# Power_driver_DAC_Connectors.net
KiCad netlist of a schematic drawn in Altium Designer
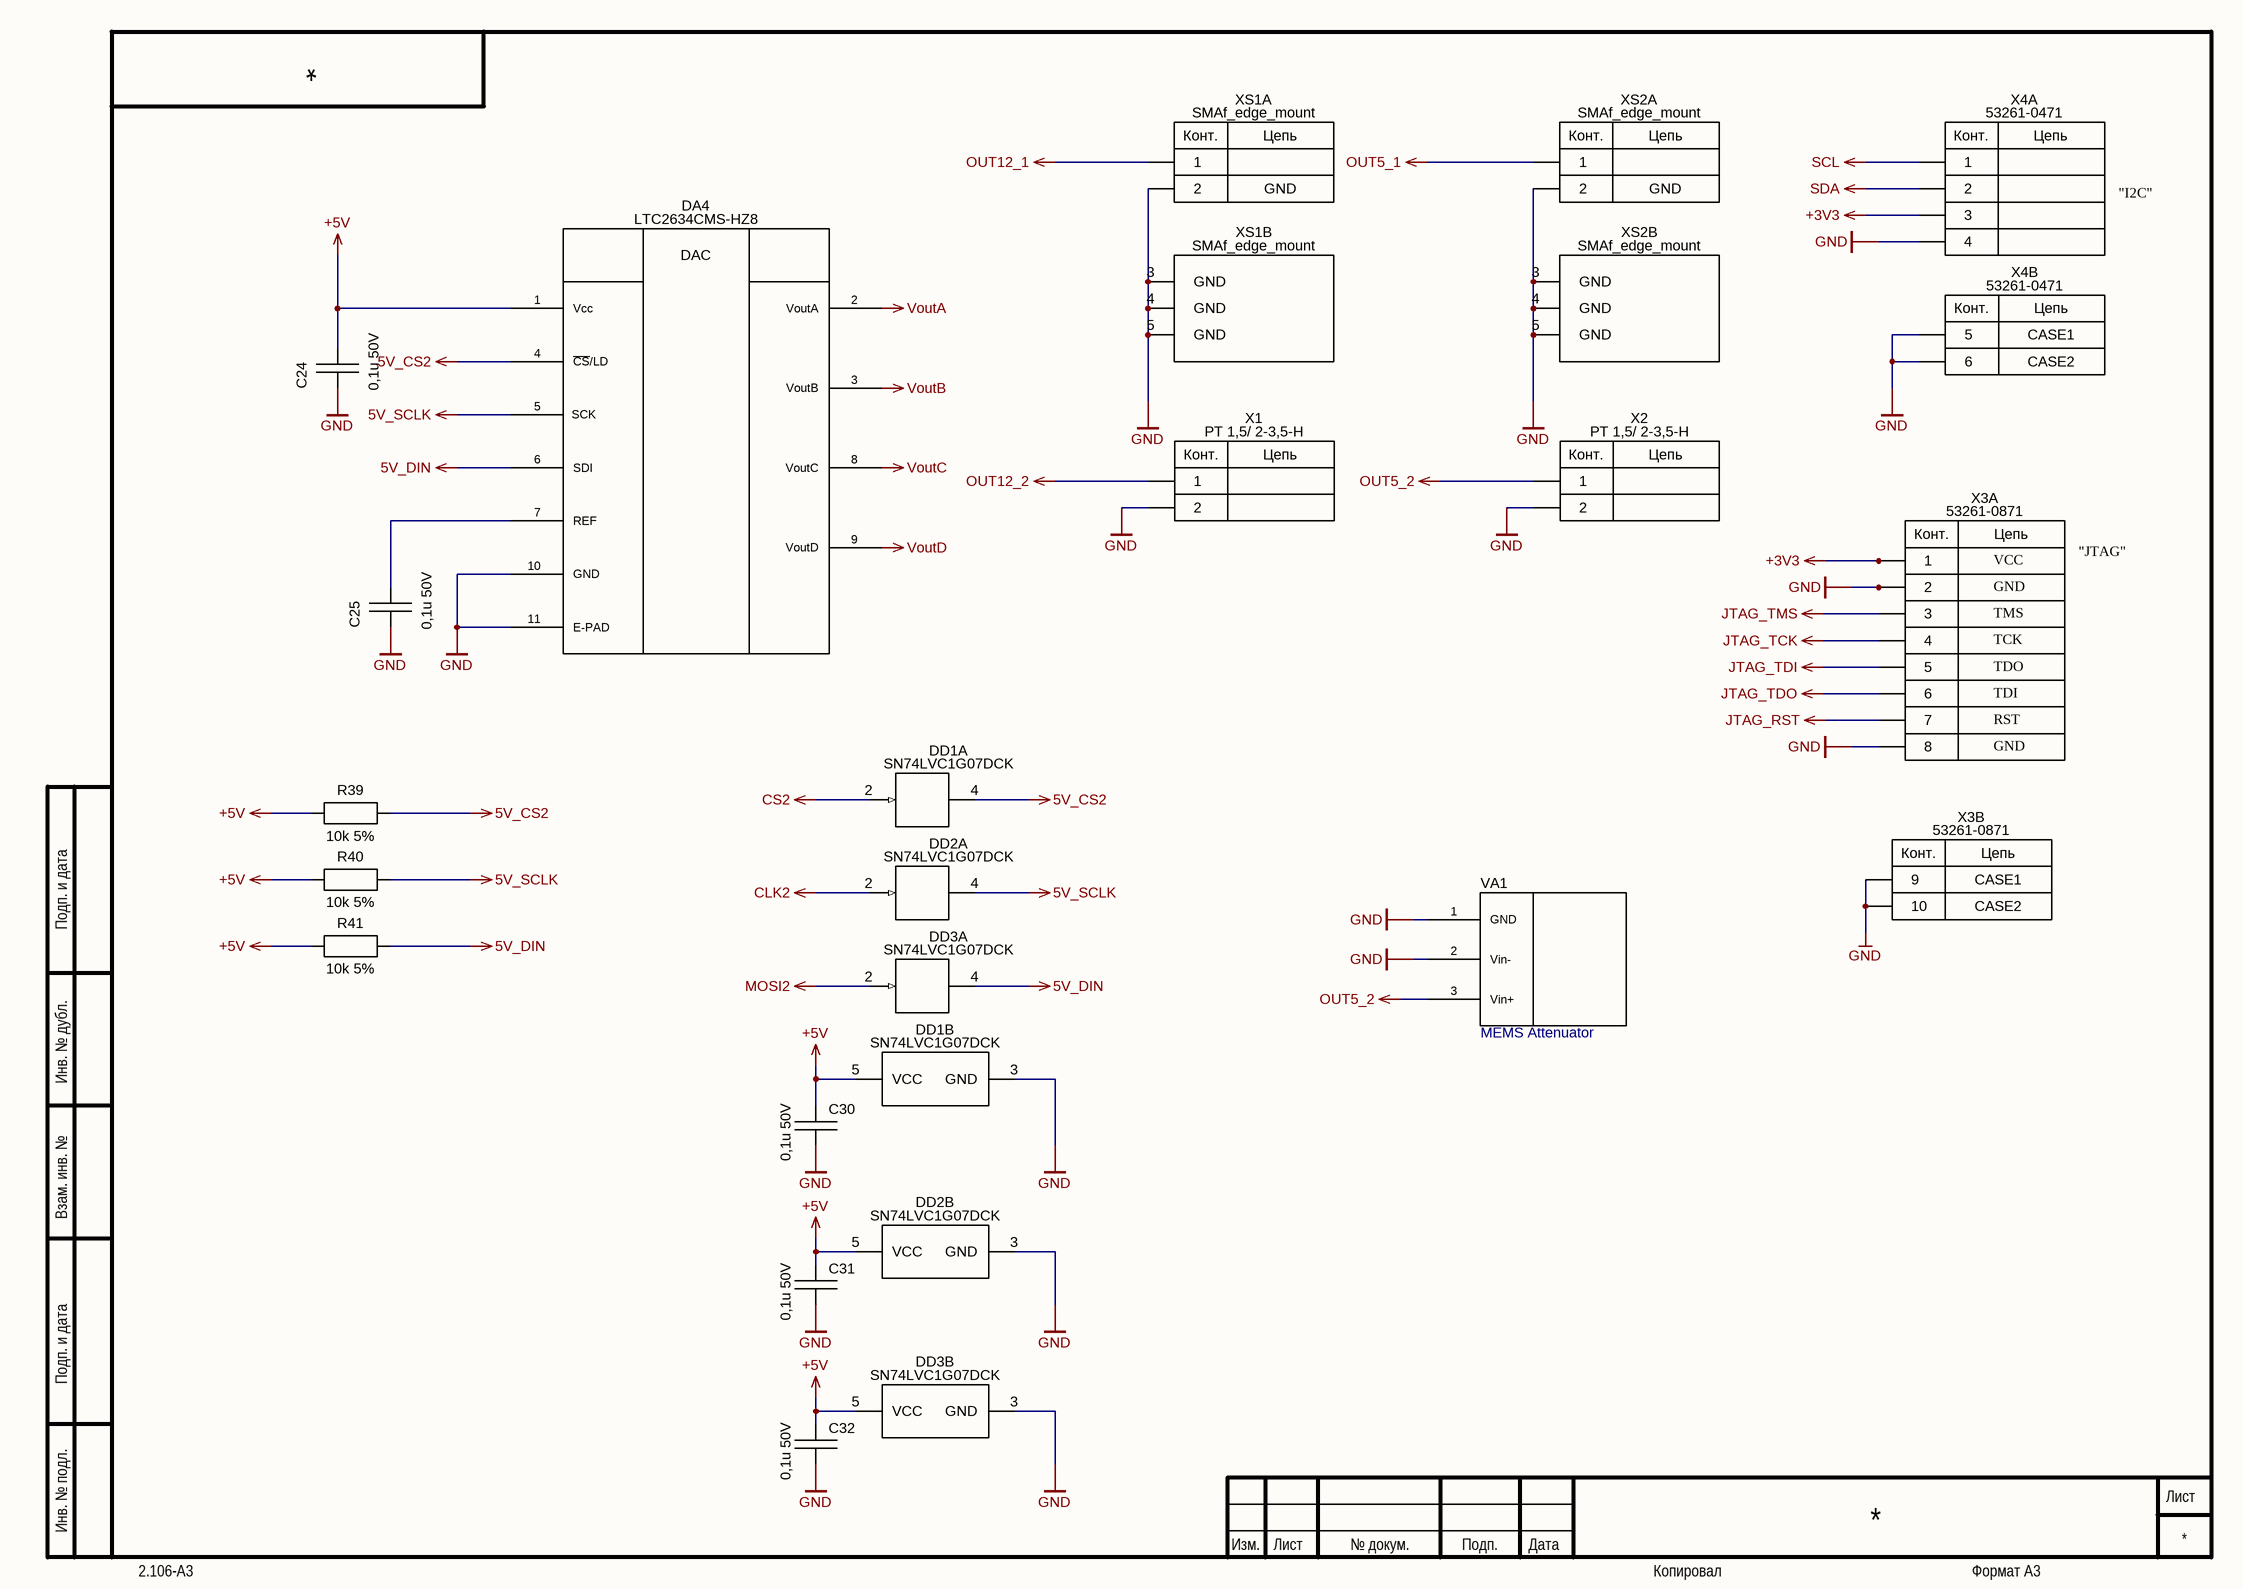
[diagram p0: Power_driver_DAC_Connectors.SchDoc]

(export (version "E")
  (design (tool "Eeschema 10.0.6"))
  (components
    (comp (ref "C24")
      (value "0,1u 50V")
      (footprint "C0603_CAPC1608X09N")
      (description "Конденсатор керамический (MLCC) общего назначения 0603")
      (fields
        (field (name "PARTNUMBER") "CC0603KRX7R9BB104")
        (field (name "MANUFACTURER") "YAGEO")
        (field (name "DESIGNER") "Dudarev")
      )
      (libsource (lib "RQCLib") (part "Capacitor"))
    )
    (comp (ref "C25")
      (value "0,1u 50V")
      (footprint "C0603_CAPC1608X09N")
      (description "Конденсатор керамический (MLCC) общего назначения 0603")
      (fields
        (field (name "PARTNUMBER") "CC0603KRX7R9BB104")
        (field (name "MANUFACTURER") "YAGEO")
        (field (name "DESIGNER") "Dudarev")
      )
      (libsource (lib "RQCLib") (part "Capacitor"))
    )
    (comp (ref "C30")
      (value "0,1u 50V")
      (footprint "C0603_CAPC1608X09N")
      (description "Конденсатор керамический (MLCC) общего назначения 0603")
      (fields
        (field (name "PARTNUMBER") "CC0603KRX7R9BB104")
        (field (name "MANUFACTURER") "YAGEO")
        (field (name "DESIGNER") "Dudarev")
      )
      (libsource (lib "RQCLib") (part "Capacitor"))
    )
    (comp (ref "C31")
      (value "0,1u 50V")
      (footprint "C0603_CAPC1608X09N")
      (description "Конденсатор керамический (MLCC) общего назначения 0603")
      (fields
        (field (name "PARTNUMBER") "CC0603KRX7R9BB104")
        (field (name "MANUFACTURER") "YAGEO")
        (field (name "DESIGNER") "Dudarev")
      )
      (libsource (lib "RQCLib") (part "Capacitor"))
    )
    (comp (ref "C32")
      (value "0,1u 50V")
      (footprint "C0603_CAPC1608X09N")
      (description "Конденсатор керамический (MLCC) общего назначения 0603")
      (fields
        (field (name "PARTNUMBER") "CC0603KRX7R9BB104")
        (field (name "MANUFACTURER") "YAGEO")
        (field (name "DESIGNER") "Dudarev")
      )
      (libsource (lib "RQCLib") (part "Capacitor"))
    )
    (comp (ref "DA4")
      (value "LTC2634CMS-HZ8")
      (footprint "MSOP50P500X110_HS-11N")
      (description "SPI  Vout quad DAC with internal reference. MSOP 10")
      (libsource (lib "IC_DAC") (part "LTC2634CMS-HZ8"))
    )
    (comp (ref "DD1")
      (value "SN74LVC1G07DCK")
      (footprint "SC70_SOT65P210X110-5N")
      (description "Single buffer\\driver with open-drain outputs for 1.65 - 5.5V VCC operation SC70")
      (fields (field (name "MANUFACTURER") "TI") (field (name "DESIGNER") "Dudarev"))
      (libsource (lib "RQCLib") (part "SN74LVC1G07"))
    )
    (comp (ref "DD2")
      (value "SN74LVC1G07DCK")
      (footprint "SC70_SOT65P210X110-5N")
      (description "Single buffer\\driver with open-drain outputs for 1.65 - 5.5V VCC operation SC70")
      (fields (field (name "MANUFACTURER") "TI") (field (name "DESIGNER") "Dudarev"))
      (libsource (lib "RQCLib") (part "SN74LVC1G07"))
    )
    (comp (ref "DD3")
      (value "SN74LVC1G07DCK")
      (footprint "SC70_SOT65P210X110-5N")
      (description "Single buffer\\driver with open-drain outputs for 1.65 - 5.5V VCC operation SC70")
      (fields (field (name "MANUFACTURER") "TI") (field (name "DESIGNER") "Dudarev"))
      (libsource (lib "RQCLib") (part "SN74LVC1G07"))
    )
    (comp (ref "R39")
      (value "10k 5%")
      (footprint "R0603_RESC1608X06N")
      (description "Резистор толстопленочный общего назначения 0603")
      (fields
        (field (name "PARTNUMBER") "RC0603JR-0710KL")
        (field (name "MANUFACTURER") "YAGEO")
        (field (name "DESIGNER") "Dudarev")
      )
      (libsource (lib "RQCLib") (part "Resistor"))
    )
    (comp (ref "R40")
      (value "10k 5%")
      (footprint "R0603_RESC1608X06N")
      (description "Резистор толстопленочный общего назначения 0603")
      (fields
        (field (name "PARTNUMBER") "RC0603JR-0710KL")
        (field (name "MANUFACTURER") "YAGEO")
        (field (name "DESIGNER") "Dudarev")
      )
      (libsource (lib "RQCLib") (part "Resistor"))
    )
    (comp (ref "R41")
      (value "10k 5%")
      (footprint "R0603_RESC1608X06N")
      (description "Резистор толстопленочный общего назначения 0603")
      (fields
        (field (name "PARTNUMBER") "RC0603JR-0710KL")
        (field (name "MANUFACTURER") "YAGEO")
        (field (name "DESIGNER") "Dudarev")
      )
      (libsource (lib "RQCLib") (part "Resistor"))
    )
    (comp (ref "VA1")
      (value "MEMS Attenuator")
      (footprint "Attenuator")
      (libsource (lib "IC_Misc") (part "MEMS Attenuator"))
    )
    (comp (ref "X1")
      (value "PT 1,5/ 2-3,5-H")
      (footprint "PT 1,5/ 2-3,5-H")
      (description "PT 1,5/ 2-3,5-H Terminal Block Connector. Strait")
      (libsource (lib "Connector_Misc") (part "PT 1,5/ 2-3,5-H"))
    )
    (comp (ref "X2")
      (value "PT 1,5/ 2-3,5-H")
      (footprint "PT 1,5/ 2-3,5-H")
      (description "PT 1,5/ 2-3,5-H Terminal Block Connector. Strait")
      (libsource (lib "Connector_Misc") (part "PT 1,5/ 2-3,5-H"))
    )
    (comp (ref "X3")
      (value "53261-0871")
      (footprint "53261-0871")
      (description "PicoBlade Header, 1,25mm Pitch, 1 Row, 8 Circuits, Right Angle, SMT")
      (fields (field (name "MANUFACTURER") "Molex") (field (name "DESIGNER") "Martynov"))
      (libsource (lib "RQCLib") (part "X8_2CASE"))
    )
    (comp (ref "X4")
      (value "53261-0471")
      (footprint "53261-0471")
      (description "PicoBlade Header, 1,25mm Pitch, 1 Row, 4 Circuits, Right Angle, SMT")
      (fields (field (name "MANUFACTURER") "Molex") (field (name "DESIGNER") "Martynov"))
      (libsource (lib "RQCLib") (part "X4_2CASE"))
    )
    (comp (ref "XS1")
      (value "SMAf_edge_mount")
      (footprint "142-0701-851")
      (description "RF COAXIAL CONNECTOR 50 Ohms, 18GHz, SMA FEMALE,  PCB 1,5mm edge mounted, SMT")
      (fields
        (field (name "PARTNUMBER") "142-0701-851")
        (field (name "MANUFACTURER") "Johnson")
        (field (name "DESIGNER") "Pashinskiy")
      )
      (libsource (lib "RQCLib") (part "SMA"))
    )
    (comp (ref "XS2")
      (value "SMAf_edge_mount")
      (footprint "142-0701-851")
      (description "RF COAXIAL CONNECTOR 50 Ohms, 18GHz, SMA FEMALE,  PCB 1,5mm edge mounted, SMT")
      (fields
        (field (name "PARTNUMBER") "142-0701-851")
        (field (name "MANUFACTURER") "Johnson")
        (field (name "DESIGNER") "Pashinskiy")
      )
      (libsource (lib "RQCLib") (part "SMA"))
    )
  )
  (nets
    (net (code "1") (name "+3V3") (class "Default")
      (node (ref "X3") (pin "1") (pinfunction "1_1") (pintype "passive"))
      (node (ref "X4") (pin "3") (pinfunction "3_3") (pintype "passive"))
    )
    (net (code "2") (name "+5V") (class "Default")
      (node (ref "C24") (pin "2") (pinfunction "2_2") (pintype "passive"))
      (node (ref "C30") (pin "1") (pinfunction "1_1") (pintype "passive"))
      (node (ref "C31") (pin "1") (pinfunction "1_1") (pintype "passive"))
      (node (ref "C32") (pin "1") (pinfunction "1_1") (pintype "passive"))
      (node (ref "DA4") (pin "1") (pinfunction "Vcc_1") (pintype "power_in"))
      (node (ref "DD1") (pin "5") (pinfunction "VCC_5") (pintype "power_in"))
      (node (ref "DD2") (pin "5") (pinfunction "VCC_5") (pintype "power_in"))
      (node (ref "DD3") (pin "5") (pinfunction "VCC_5") (pintype "power_in"))
      (node (ref "R39") (pin "1") (pinfunction "1_1") (pintype "passive"))
      (node (ref "R40") (pin "1") (pinfunction "1_1") (pintype "passive"))
      (node (ref "R41") (pin "1") (pinfunction "1_1") (pintype "passive"))
    )
    (net (code "3") (name "5V_CS2") (class "Default")
      (node (ref "DA4") (pin "4") (pinfunction "~{CS}/LD_4") (pintype "passive"))
      (node (ref "DD1") (pin "4") (pinfunction "Y_4") (pintype "open_collector"))
      (node (ref "R39") (pin "2") (pinfunction "2_2") (pintype "passive"))
    )
    (net (code "4") (name "5V_DIN") (class "Default")
      (node (ref "DA4") (pin "6") (pinfunction "SDI_6") (pintype "power_in"))
      (node (ref "DD3") (pin "4") (pinfunction "Y_4") (pintype "open_collector"))
      (node (ref "R41") (pin "2") (pinfunction "2_2") (pintype "passive"))
    )
    (net (code "5") (name "5V_SCLK") (class "Default")
      (node (ref "DA4") (pin "5") (pinfunction "SCK_5") (pintype "passive"))
      (node (ref "DD2") (pin "4") (pinfunction "Y_4") (pintype "open_collector"))
      (node (ref "R40") (pin "2") (pinfunction "2_2") (pintype "passive"))
    )
    (net (code "6") (name "CLK2") (class "Default")
      (node (ref "DD2") (pin "2") (pinfunction "A_2") (pintype "input"))
    )
    (net (code "7") (name "CS2") (class "Default")
      (node (ref "DD1") (pin "2") (pinfunction "A_2") (pintype "input"))
    )
    (net (code "8") (name "GND") (class "Default")
      (node (ref "C24") (pin "1") (pinfunction "1_1") (pintype "passive"))
      (node (ref "C25") (pin "1") (pinfunction "1_1") (pintype "passive"))
      (node (ref "C30") (pin "2") (pinfunction "2_2") (pintype "passive"))
      (node (ref "C31") (pin "2") (pinfunction "2_2") (pintype "passive"))
      (node (ref "C32") (pin "2") (pinfunction "2_2") (pintype "passive"))
      (node (ref "DA4") (pin "10") (pinfunction "GND_10") (pintype "power_in"))
      (node (ref "DA4") (pin "11") (pinfunction "E-PAD_11") (pintype "power_in"))
      (node (ref "DD1") (pin "3") (pinfunction "GND_3") (pintype "power_in"))
      (node (ref "DD2") (pin "3") (pinfunction "GND_3") (pintype "power_in"))
      (node (ref "DD3") (pin "3") (pinfunction "GND_3") (pintype "power_in"))
      (node (ref "VA1") (pin "1") (pinfunction "GND_1") (pintype "passive"))
      (node (ref "VA1") (pin "2") (pinfunction "Vin-_2") (pintype "passive"))
      (node (ref "X1") (pin "2") (pinfunction "2_2") (pintype "passive"))
      (node (ref "X2") (pin "2") (pinfunction "2_2") (pintype "passive"))
      (node (ref "X3") (pin "10") (pinfunction "10_10") (pintype "passive"))
      (node (ref "X3") (pin "2") (pinfunction "2_2") (pintype "passive"))
      (node (ref "X3") (pin "8") (pinfunction "8_8") (pintype "passive"))
      (node (ref "X3") (pin "9") (pinfunction "9_9") (pintype "passive"))
      (node (ref "X4") (pin "4") (pinfunction "4_4") (pintype "passive"))
      (node (ref "X4") (pin "5") (pinfunction "5_5") (pintype "passive"))
      (node (ref "X4") (pin "6") (pinfunction "6_6") (pintype "passive"))
      (node (ref "XS1") (pin "2") (pinfunction "2_2") (pintype "passive"))
      (node (ref "XS1") (pin "3") (pinfunction "GND_3") (pintype "passive"))
      (node (ref "XS1") (pin "4") (pinfunction "GND_4") (pintype "passive"))
      (node (ref "XS1") (pin "5") (pinfunction "GND_5") (pintype "passive"))
      (node (ref "XS2") (pin "2") (pinfunction "2_2") (pintype "passive"))
      (node (ref "XS2") (pin "3") (pinfunction "GND_3") (pintype "passive"))
      (node (ref "XS2") (pin "4") (pinfunction "GND_4") (pintype "passive"))
      (node (ref "XS2") (pin "5") (pinfunction "GND_5") (pintype "passive"))
    )
    (net (code "9") (name "JTAG_RST") (class "Default")
      (node (ref "X3") (pin "7") (pinfunction "7_7") (pintype "passive"))
    )
    (net (code "10") (name "JTAG_TCK") (class "Default")
      (node (ref "X3") (pin "4") (pinfunction "4_4") (pintype "passive"))
    )
    (net (code "11") (name "JTAG_TDI") (class "Default")
      (node (ref "X3") (pin "5") (pinfunction "5_5") (pintype "passive"))
    )
    (net (code "12") (name "JTAG_TDO") (class "Default")
      (node (ref "X3") (pin "6") (pinfunction "6_6") (pintype "passive"))
    )
    (net (code "13") (name "JTAG_TMS") (class "Default")
      (node (ref "X3") (pin "3") (pinfunction "3_3") (pintype "passive"))
    )
    (net (code "14") (name "MOSI2") (class "Default")
      (node (ref "DD3") (pin "2") (pinfunction "A_2") (pintype "input"))
    )
    (net (code "15") (name "Net-(DA4-REF)") (class "Default")
      (node (ref "C25") (pin "2") (pinfunction "2_2") (pintype "passive"))
      (node (ref "DA4") (pin "7") (pinfunction "REF_7") (pintype "power_in"))
    )
    (net (code "16") (name "OUT5_1") (class "Default")
      (node (ref "XS2") (pin "1") (pinfunction "1_1") (pintype "passive"))
    )
    (net (code "17") (name "OUT5_2") (class "Default")
      (node (ref "VA1") (pin "3") (pinfunction "Vin+_3") (pintype "passive"))
      (node (ref "X2") (pin "1") (pinfunction "1_1") (pintype "passive"))
    )
    (net (code "18") (name "OUT12_1") (class "Default")
      (node (ref "XS1") (pin "1") (pinfunction "1_1") (pintype "passive"))
    )
    (net (code "19") (name "OUT12_2") (class "Default")
      (node (ref "X1") (pin "1") (pinfunction "1_1") (pintype "passive"))
    )
    (net (code "20") (name "SCL") (class "Default")
      (node (ref "X4") (pin "1") (pinfunction "1_1") (pintype "passive"))
    )
    (net (code "21") (name "SDA") (class "Default")
      (node (ref "X4") (pin "2") (pinfunction "2_2") (pintype "passive"))
    )
    (net (code "22") (name "VoutA") (class "Default")
      (node (ref "DA4") (pin "2") (pinfunction "VoutA_2") (pintype "passive"))
    )
    (net (code "23") (name "VoutB") (class "Default")
      (node (ref "DA4") (pin "3") (pinfunction "VoutB_3") (pintype "passive"))
    )
    (net (code "24") (name "VoutC") (class "Default")
      (node (ref "DA4") (pin "8") (pinfunction "VoutC_8") (pintype "passive"))
    )
    (net (code "25") (name "VoutD") (class "Default")
      (node (ref "DA4") (pin "9") (pinfunction "VoutD_9") (pintype "power_in"))
    )
  )
)
